# Komplet_0_1.net
KiCad netlist of a schematic drawn in EAGLE
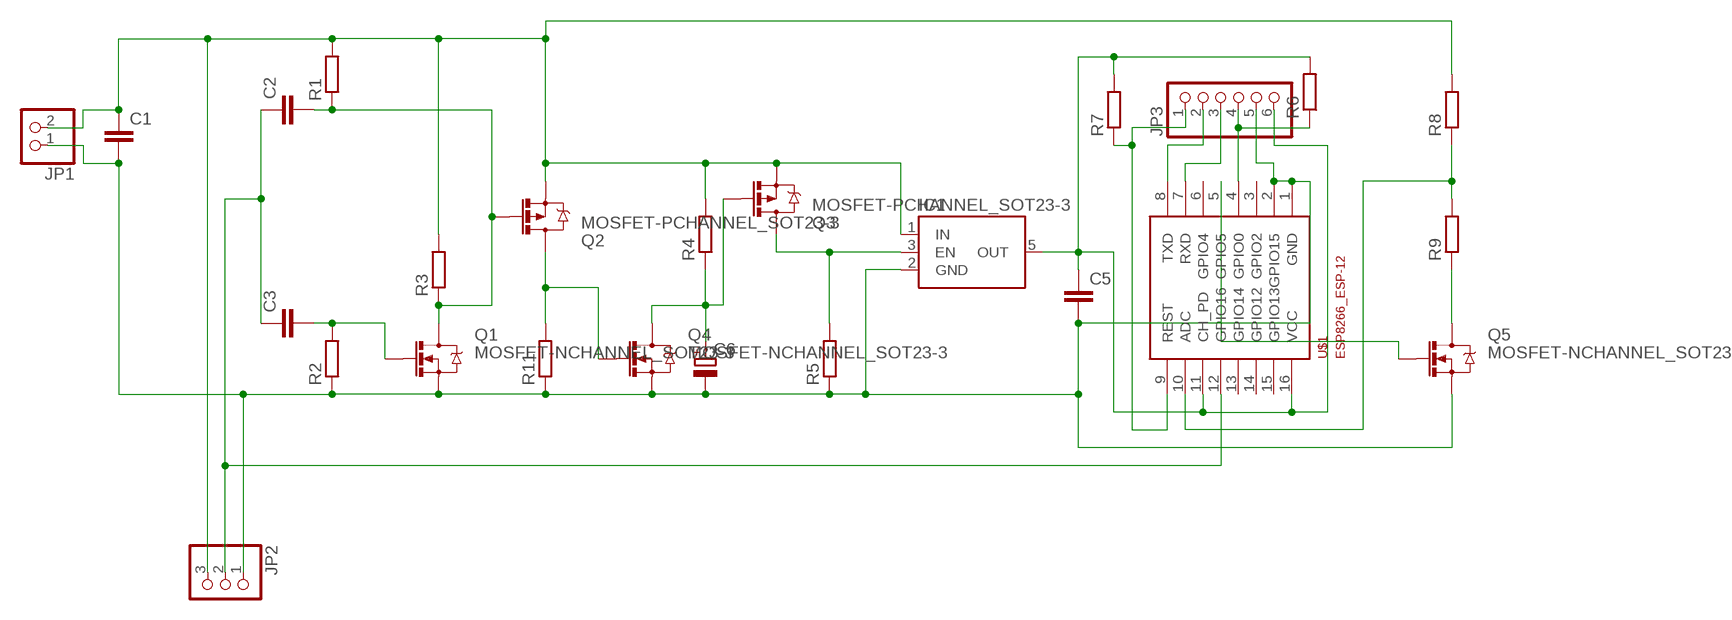
[diagram p0: schematic, sheet 1]

(export (version "E")
  (design (tool "Eeschema 10.0.6"))
  (components
    (comp (ref "C1")
      (value "C-EUC0805")
      (footprint "eagle-import:C0805")
      (libsource (lib "eagle-import") (part "C-EUC0805"))
    )
    (comp (ref "C2")
      (value "C-EUC0805")
      (footprint "eagle-import:C0805")
      (libsource (lib "eagle-import") (part "C-EUC0805"))
    )
    (comp (ref "C3")
      (value "C-EUC0805")
      (footprint "eagle-import:C0805")
      (libsource (lib "eagle-import") (part "C-EUC0805"))
    )
    (comp (ref "C5")
      (value "C-EUC0805")
      (footprint "eagle-import:C0805")
      (libsource (lib "eagle-import") (part "C-EUC0805"))
    )
    (comp (ref "C6")
      (value "CPOL-EU153CLV-0807")
      (footprint "eagle-import:153CLV-0807")
      (libsource (lib "eagle-import") (part "CPOL-EU153CLV-0807"))
    )
    (comp (ref "IC1")
      (value "TLV700XX_DDC")
      (footprint "eagle-import:SOT23-5")
      (fields (field (name "PARTNUM") "TLV700??DDC?"))
      (libsource (lib "eagle-import") (part "TLV700XX_DDC"))
    )
    (comp (ref "JP1")
      (value "PINHD-1X02_2.54")
      (footprint "eagle-import:1X02")
      (libsource (lib "eagle-import") (part "PINHD-1X02_2.54"))
    )
    (comp (ref "JP2")
      (value "PINHD-1X03_2.54")
      (footprint "eagle-import:1X03")
      (libsource (lib "eagle-import") (part "PINHD-1X03_2.54"))
    )
    (comp (ref "JP3")
      (value "PINHD-1X06_2.54")
      (footprint "eagle-import:1X06")
      (libsource (lib "eagle-import") (part "PINHD-1X06_2.54"))
    )
    (comp (ref "Q1")
      (value "MOSFET-NCHANNEL_SOT23-3")
      (footprint "eagle-import:SOT23-3")
      (libsource (lib "eagle-import") (part "MOSFET-NCHANNEL_SOT23-3"))
    )
    (comp (ref "Q2")
      (value "MOSFET-PCHANNEL_SOT23-3")
      (footprint "eagle-import:SOT23-3")
      (libsource (lib "eagle-import") (part "MOSFET-PCHANNEL_SOT23-3"))
    )
    (comp (ref "Q3")
      (value "MOSFET-PCHANNEL_SOT23-3")
      (footprint "eagle-import:SOT23-3")
      (libsource (lib "eagle-import") (part "MOSFET-PCHANNEL_SOT23-3"))
    )
    (comp (ref "Q4")
      (value "MOSFET-NCHANNEL_SOT23-3")
      (footprint "eagle-import:SOT23-3")
      (libsource (lib "eagle-import") (part "MOSFET-NCHANNEL_SOT23-3"))
    )
    (comp (ref "Q5")
      (value "MOSFET-NCHANNEL_SOT23-3")
      (footprint "eagle-import:SOT23-3")
      (libsource (lib "eagle-import") (part "MOSFET-NCHANNEL_SOT23-3"))
    )
    (comp (ref "R1")
      (value "R-EU_R0805")
      (footprint "eagle-import:R0805")
      (libsource (lib "eagle-import") (part "R-EU_R0805"))
    )
    (comp (ref "R2")
      (value "R-EU_R0805")
      (footprint "eagle-import:R0805")
      (libsource (lib "eagle-import") (part "R-EU_R0805"))
    )
    (comp (ref "R3")
      (value "R-EU_R0805")
      (footprint "eagle-import:R0805")
      (libsource (lib "eagle-import") (part "R-EU_R0805"))
    )
    (comp (ref "R4")
      (value "R-EU_R0805")
      (footprint "eagle-import:R0805")
      (libsource (lib "eagle-import") (part "R-EU_R0805"))
    )
    (comp (ref "R5")
      (value "R-EU_R0805")
      (footprint "eagle-import:R0805")
      (libsource (lib "eagle-import") (part "R-EU_R0805"))
    )
    (comp (ref "R6")
      (value "R-EU_R0805")
      (footprint "eagle-import:R0805")
      (libsource (lib "eagle-import") (part "R-EU_R0805"))
    )
    (comp (ref "R7")
      (value "R-EU_R0805")
      (footprint "eagle-import:R0805")
      (libsource (lib "eagle-import") (part "R-EU_R0805"))
    )
    (comp (ref "R8")
      (value "R-EU_R0805")
      (footprint "eagle-import:R0805")
      (libsource (lib "eagle-import") (part "R-EU_R0805"))
    )
    (comp (ref "R9")
      (value "R-EU_R0805")
      (footprint "eagle-import:R0805")
      (libsource (lib "eagle-import") (part "R-EU_R0805"))
    )
    (comp (ref "R11")
      (value "R-EU_R1206")
      (footprint "eagle-import:R1206")
      (libsource (lib "eagle-import") (part "R-EU_R1206"))
    )
    (comp (ref "U$1")
      (value "ESP8266_ESP-12")
      (footprint "eagle-import:ESP8266-ESP12")
      (libsource (lib "eagle-import") (part "ESP8266_ESP-12"))
    )
  )
  (nets
    (net (code "1") (name "Net-(IC1-EN)") (class "Default")
      (node (ref "IC1") (pin "3") (pinfunction "EN_3") (pintype "bidirectional"))
      (node (ref "Q3") (pin "3") (pinfunction "D_3") (pintype "passive"))
      (node (ref "R5") (pin "2") (pinfunction "2_2") (pintype "passive"))
    )
    (net (code "2") (name "Net-(IC1-GND)") (class "Default")
      (node (ref "C1") (pin "2") (pinfunction "2_2") (pintype "passive"))
      (node (ref "C5") (pin "2") (pinfunction "2_2") (pintype "passive"))
      (node (ref "C6") (pin "-") (pinfunction "-_-") (pintype "passive"))
      (node (ref "IC1") (pin "2") (pinfunction "GND_2") (pintype "bidirectional"))
      (node (ref "JP1") (pin "1") (pinfunction "1_1") (pintype "passive"))
      (node (ref "JP2") (pin "1") (pinfunction "1_1") (pintype "passive"))
      (node (ref "JP3") (pin "5") (pinfunction "5_5") (pintype "passive"))
      (node (ref "Q1") (pin "2") (pinfunction "S_2") (pintype "passive"))
      (node (ref "Q4") (pin "2") (pinfunction "S_2") (pintype "passive"))
      (node (ref "Q5") (pin "2") (pinfunction "S_2") (pintype "passive"))
      (node (ref "R11") (pin "1") (pinfunction "1_1") (pintype "passive"))
      (node (ref "R2") (pin "1") (pinfunction "1_1") (pintype "passive"))
      (node (ref "R5") (pin "1") (pinfunction "1_1") (pintype "passive"))
      (node (ref "U$1") (pin "1") (pinfunction "GND_1") (pintype "bidirectional"))
      (node (ref "U$1") (pin "2") (pinfunction "GPIO15_2") (pintype "bidirectional"))
    )
    (net (code "3") (name "Net-(IC1-IN)") (class "Default")
      (node (ref "C1") (pin "1") (pinfunction "1_1") (pintype "passive"))
      (node (ref "IC1") (pin "1") (pinfunction "IN_1") (pintype "bidirectional"))
      (node (ref "JP1") (pin "2") (pinfunction "2_2") (pintype "passive"))
      (node (ref "JP2") (pin "3") (pinfunction "3_3") (pintype "passive"))
      (node (ref "Q2") (pin "2") (pinfunction "S_2") (pintype "passive"))
      (node (ref "Q3") (pin "2") (pinfunction "S_2") (pintype "passive"))
      (node (ref "R1") (pin "2") (pinfunction "2_2") (pintype "passive"))
      (node (ref "R3") (pin "2") (pinfunction "2_2") (pintype "passive"))
      (node (ref "R4") (pin "2") (pinfunction "2_2") (pintype "passive"))
      (node (ref "R8") (pin "2") (pinfunction "2_2") (pintype "passive"))
    )
    (net (code "4") (name "Net-(IC1-OUT)") (class "Default")
      (node (ref "C5") (pin "1") (pinfunction "1_1") (pintype "passive"))
      (node (ref "IC1") (pin "5") (pinfunction "OUT_5") (pintype "bidirectional"))
      (node (ref "JP3") (pin "6") (pinfunction "6_6") (pintype "passive"))
      (node (ref "R6") (pin "2") (pinfunction "2_2") (pintype "passive"))
      (node (ref "R7") (pin "2") (pinfunction "2_2") (pintype "passive"))
      (node (ref "U$1") (pin "11") (pinfunction "CH_PD_11") (pintype "bidirectional"))
      (node (ref "U$1") (pin "16") (pinfunction "VCC_16") (pintype "bidirectional"))
    )
    (net (code "5") (name "Net-(Q1-D)") (class "Default")
      (node (ref "C2") (pin "2") (pinfunction "2_2") (pintype "passive"))
      (node (ref "Q1") (pin "3") (pinfunction "D_3") (pintype "passive"))
      (node (ref "Q2") (pin "1") (pinfunction "G_1") (pintype "passive"))
      (node (ref "R1") (pin "1") (pinfunction "1_1") (pintype "passive"))
      (node (ref "R3") (pin "1") (pinfunction "1_1") (pintype "passive"))
    )
    (net (code "6") (name "Net-(Q1-G)") (class "Default")
      (node (ref "C3") (pin "2") (pinfunction "2_2") (pintype "passive"))
      (node (ref "Q1") (pin "1") (pinfunction "G_1") (pintype "passive"))
      (node (ref "R2") (pin "2") (pinfunction "2_2") (pintype "passive"))
    )
    (net (code "7") (name "Net-(Q2-D)") (class "Default")
      (node (ref "Q2") (pin "3") (pinfunction "D_3") (pintype "passive"))
      (node (ref "Q4") (pin "1") (pinfunction "G_1") (pintype "passive"))
      (node (ref "R11") (pin "2") (pinfunction "2_2") (pintype "passive"))
    )
    (net (code "8") (name "Net-(Q3-G)") (class "Default")
      (node (ref "C6") (pin "+") (pinfunction "+_+") (pintype "passive"))
      (node (ref "Q3") (pin "1") (pinfunction "G_1") (pintype "passive"))
      (node (ref "Q4") (pin "3") (pinfunction "D_3") (pintype "passive"))
      (node (ref "R4") (pin "1") (pinfunction "1_1") (pintype "passive"))
    )
    (net (code "9") (name "Net-(Q5-D)") (class "Default")
      (node (ref "Q5") (pin "3") (pinfunction "D_3") (pintype "passive"))
      (node (ref "R9") (pin "1") (pinfunction "1_1") (pintype "passive"))
    )
    (net (code "10") (name "Net-(Q5-G)") (class "Default")
      (node (ref "Q5") (pin "1") (pinfunction "G_1") (pintype "passive"))
      (node (ref "U$1") (pin "5") (pinfunction "GPIO5_5") (pintype "bidirectional"))
    )
    (net (code "11") (name "Net-(U$1-ADC)") (class "Default")
      (node (ref "R8") (pin "1") (pinfunction "1_1") (pintype "passive"))
      (node (ref "R9") (pin "2") (pinfunction "2_2") (pintype "passive"))
      (node (ref "U$1") (pin "10") (pinfunction "ADC_10") (pintype "bidirectional"))
    )
    (net (code "12") (name "Net-(U$1-GPIO0)") (class "Default")
      (node (ref "JP3") (pin "4") (pinfunction "4_4") (pintype "passive"))
      (node (ref "R6") (pin "1") (pinfunction "1_1") (pintype "passive"))
      (node (ref "U$1") (pin "4") (pinfunction "GPIO0_4") (pintype "bidirectional"))
    )
    (net (code "13") (name "Net-(U$1-GPIO16)") (class "Default")
      (node (ref "C2") (pin "1") (pinfunction "1_1") (pintype "passive"))
      (node (ref "C3") (pin "1") (pinfunction "1_1") (pintype "passive"))
      (node (ref "JP2") (pin "2") (pinfunction "2_2") (pintype "passive"))
      (node (ref "U$1") (pin "12") (pinfunction "GPIO16_12") (pintype "bidirectional"))
    )
    (net (code "14") (name "Net-(U$1-REST)") (class "Default")
      (node (ref "JP3") (pin "1") (pinfunction "1_1") (pintype "passive"))
      (node (ref "R7") (pin "1") (pinfunction "1_1") (pintype "passive"))
      (node (ref "U$1") (pin "9") (pinfunction "REST_9") (pintype "bidirectional"))
    )
    (net (code "15") (name "Net-(U$1-RXD)") (class "Default")
      (node (ref "JP3") (pin "3") (pinfunction "3_3") (pintype "passive"))
      (node (ref "U$1") (pin "7") (pinfunction "RXD_7") (pintype "bidirectional"))
    )
    (net (code "16") (name "Net-(U$1-TXD)") (class "Default")
      (node (ref "JP3") (pin "2") (pinfunction "2_2") (pintype "passive"))
      (node (ref "U$1") (pin "8") (pinfunction "TXD_8") (pintype "bidirectional"))
    )
    (net (code "17") (name "unconnected-(U$1-GPIO2-Pad3)") (class "Default")
      (node (ref "U$1") (pin "3") (pinfunction "GPIO2_3") (pintype "bidirectional"))
    )
    (net (code "18") (name "unconnected-(U$1-GPIO4-Pad6)") (class "Default")
      (node (ref "U$1") (pin "6") (pinfunction "GPIO4_6") (pintype "bidirectional"))
    )
    (net (code "19") (name "unconnected-(U$1-GPIO12-Pad14)") (class "Default")
      (node (ref "U$1") (pin "14") (pinfunction "GPIO12_14") (pintype "bidirectional"))
    )
    (net (code "20") (name "unconnected-(U$1-GPIO13-Pad15)") (class "Default")
      (node (ref "U$1") (pin "15") (pinfunction "GPIO13_15") (pintype "bidirectional"))
    )
    (net (code "21") (name "unconnected-(U$1-GPIO14-Pad13)") (class "Default")
      (node (ref "U$1") (pin "13") (pinfunction "GPIO14_13") (pintype "bidirectional"))
    )
  )
)
